# Power.net
KiCad netlist of a schematic drawn in Altium Designer
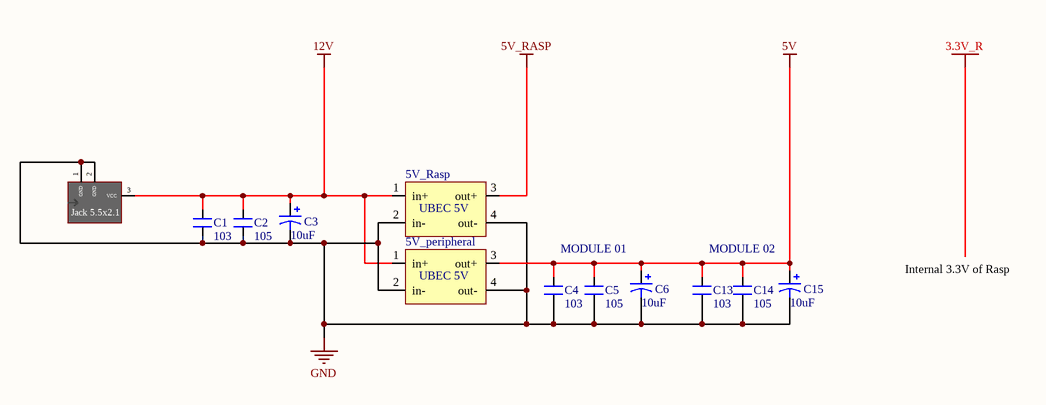
[diagram p0: Power.SchDoc]

(export (version "E")
  (design (tool "Eeschema 10.0.6"))
  (components
    (comp (ref "5V_peripheral") (value "UBEC") (footprint "UBEC") (libsource (lib "Sch") (part "UBEC")))
    (comp (ref "5V_Rasp") (value "UBEC") (footprint "UBEC") (libsource (lib "Sch") (part "UBEC")))
    (comp (ref "C1")
      (value "103")
      (footprint "CN1")
      (description "Cap np  1pF - 472pF")
      (libsource (lib "syhaunguyen") (part "CN1"))
    )
    (comp (ref "C2")
      (value "105")
      (footprint "CN1")
      (description "Cap np  1pF - 472pF")
      (libsource (lib "syhaunguyen") (part "CN1"))
    )
    (comp (ref "C3")
      (value "10uF")
      (footprint "CP2/5")
      (description "Polarized Capacitor (Surface Mount)")
      (fields (field (name "PUBLISHER") "Altium Limited"))
      (libsource (lib "syhaunguyen") (part "Cap Pol3_1"))
    )
    (comp (ref "C4")
      (value "103")
      (footprint "CN1")
      (description "Cap np  1pF - 472pF")
      (libsource (lib "syhaunguyen") (part "CN1"))
    )
    (comp (ref "C5")
      (value "105")
      (footprint "CN1")
      (description "Cap np  1pF - 472pF")
      (libsource (lib "syhaunguyen") (part "CN1"))
    )
    (comp (ref "C6")
      (value "10uF")
      (footprint "CP2/5")
      (description "Polarized Capacitor (Surface Mount)")
      (fields (field (name "PUBLISHER") "Altium Limited"))
      (libsource (lib "syhaunguyen") (part "Cap Pol3_1"))
    )
    (comp (ref "C13")
      (value "103")
      (footprint "CN1")
      (description "Cap np  1pF - 472pF")
      (libsource (lib "syhaunguyen") (part "CN1"))
    )
    (comp (ref "C14")
      (value "105")
      (footprint "CN1")
      (description "Cap np  1pF - 472pF")
      (libsource (lib "syhaunguyen") (part "CN1"))
    )
    (comp (ref "C15")
      (value "10uF")
      (footprint "CP2/5")
      (description "Polarized Capacitor (Surface Mount)")
      (fields (field (name "PUBLISHER") "Altium Limited"))
      (libsource (lib "syhaunguyen") (part "Cap Pol3_1"))
    )
    (comp (ref "J1")
      (value "5#DC Jack 2.54mm")
      (footprint "5#DC Jack 2.54mm")
      (libsource (lib "Sch") (part "5#DC Jack 2.54mm"))
    )
  )
  (nets
    (net (code "1") (name "5V") (class "Default")
      (node (ref "5V_peripheral") (pin "3") (pinfunction "out+_3") (pintype "passive"))
      (node (ref "C13") (pin "2") (pinfunction "2_2") (pintype "passive"))
      (node (ref "C14") (pin "2") (pinfunction "2_2") (pintype "passive"))
      (node (ref "C15") (pin "1") (pinfunction "1_1") (pintype "passive"))
      (node (ref "C4") (pin "2") (pinfunction "2_2") (pintype "passive"))
      (node (ref "C5") (pin "2") (pinfunction "2_2") (pintype "passive"))
      (node (ref "C6") (pin "1") (pinfunction "1_1") (pintype "passive"))
    )
    (net (code "2") (name "5V_RASP") (class "Default")
      (node (ref "5V_Rasp") (pin "3") (pinfunction "out+_3") (pintype "passive"))
    )
    (net (code "3") (name "12V") (class "Default")
      (node (ref "5V_Rasp") (pin "1") (pinfunction "in+_1") (pintype "passive"))
      (node (ref "5V_peripheral") (pin "1") (pinfunction "in+_1") (pintype "passive"))
      (node (ref "C1") (pin "2") (pinfunction "2_2") (pintype "passive"))
      (node (ref "C2") (pin "2") (pinfunction "2_2") (pintype "passive"))
      (node (ref "C3") (pin "1") (pinfunction "1_1") (pintype "passive"))
      (node (ref "J1") (pin "3") (pinfunction "VCC_3") (pintype "passive"))
    )
    (net (code "4") (name "GND") (class "Default")
      (node (ref "5V_Rasp") (pin "2") (pinfunction "in-_2") (pintype "passive"))
      (node (ref "5V_Rasp") (pin "4") (pinfunction "out-_4") (pintype "passive"))
      (node (ref "5V_peripheral") (pin "2") (pinfunction "in-_2") (pintype "passive"))
      (node (ref "5V_peripheral") (pin "4") (pinfunction "out-_4") (pintype "passive"))
      (node (ref "C1") (pin "1") (pinfunction "1_1") (pintype "passive"))
      (node (ref "C13") (pin "1") (pinfunction "1_1") (pintype "passive"))
      (node (ref "C14") (pin "1") (pinfunction "1_1") (pintype "passive"))
      (node (ref "C15") (pin "2") (pinfunction "2_2") (pintype "passive"))
      (node (ref "C2") (pin "1") (pinfunction "1_1") (pintype "passive"))
      (node (ref "C3") (pin "2") (pinfunction "2_2") (pintype "passive"))
      (node (ref "C4") (pin "1") (pinfunction "1_1") (pintype "passive"))
      (node (ref "C5") (pin "1") (pinfunction "1_1") (pintype "passive"))
      (node (ref "C6") (pin "2") (pinfunction "2_2") (pintype "passive"))
      (node (ref "J1") (pin "1") (pinfunction "GND_1") (pintype "passive"))
      (node (ref "J1") (pin "2") (pinfunction "GND_2") (pintype "passive"))
    )
  )
)
